# 5Vboostproto.net
KiCad netlist of a schematic drawn in EAGLE
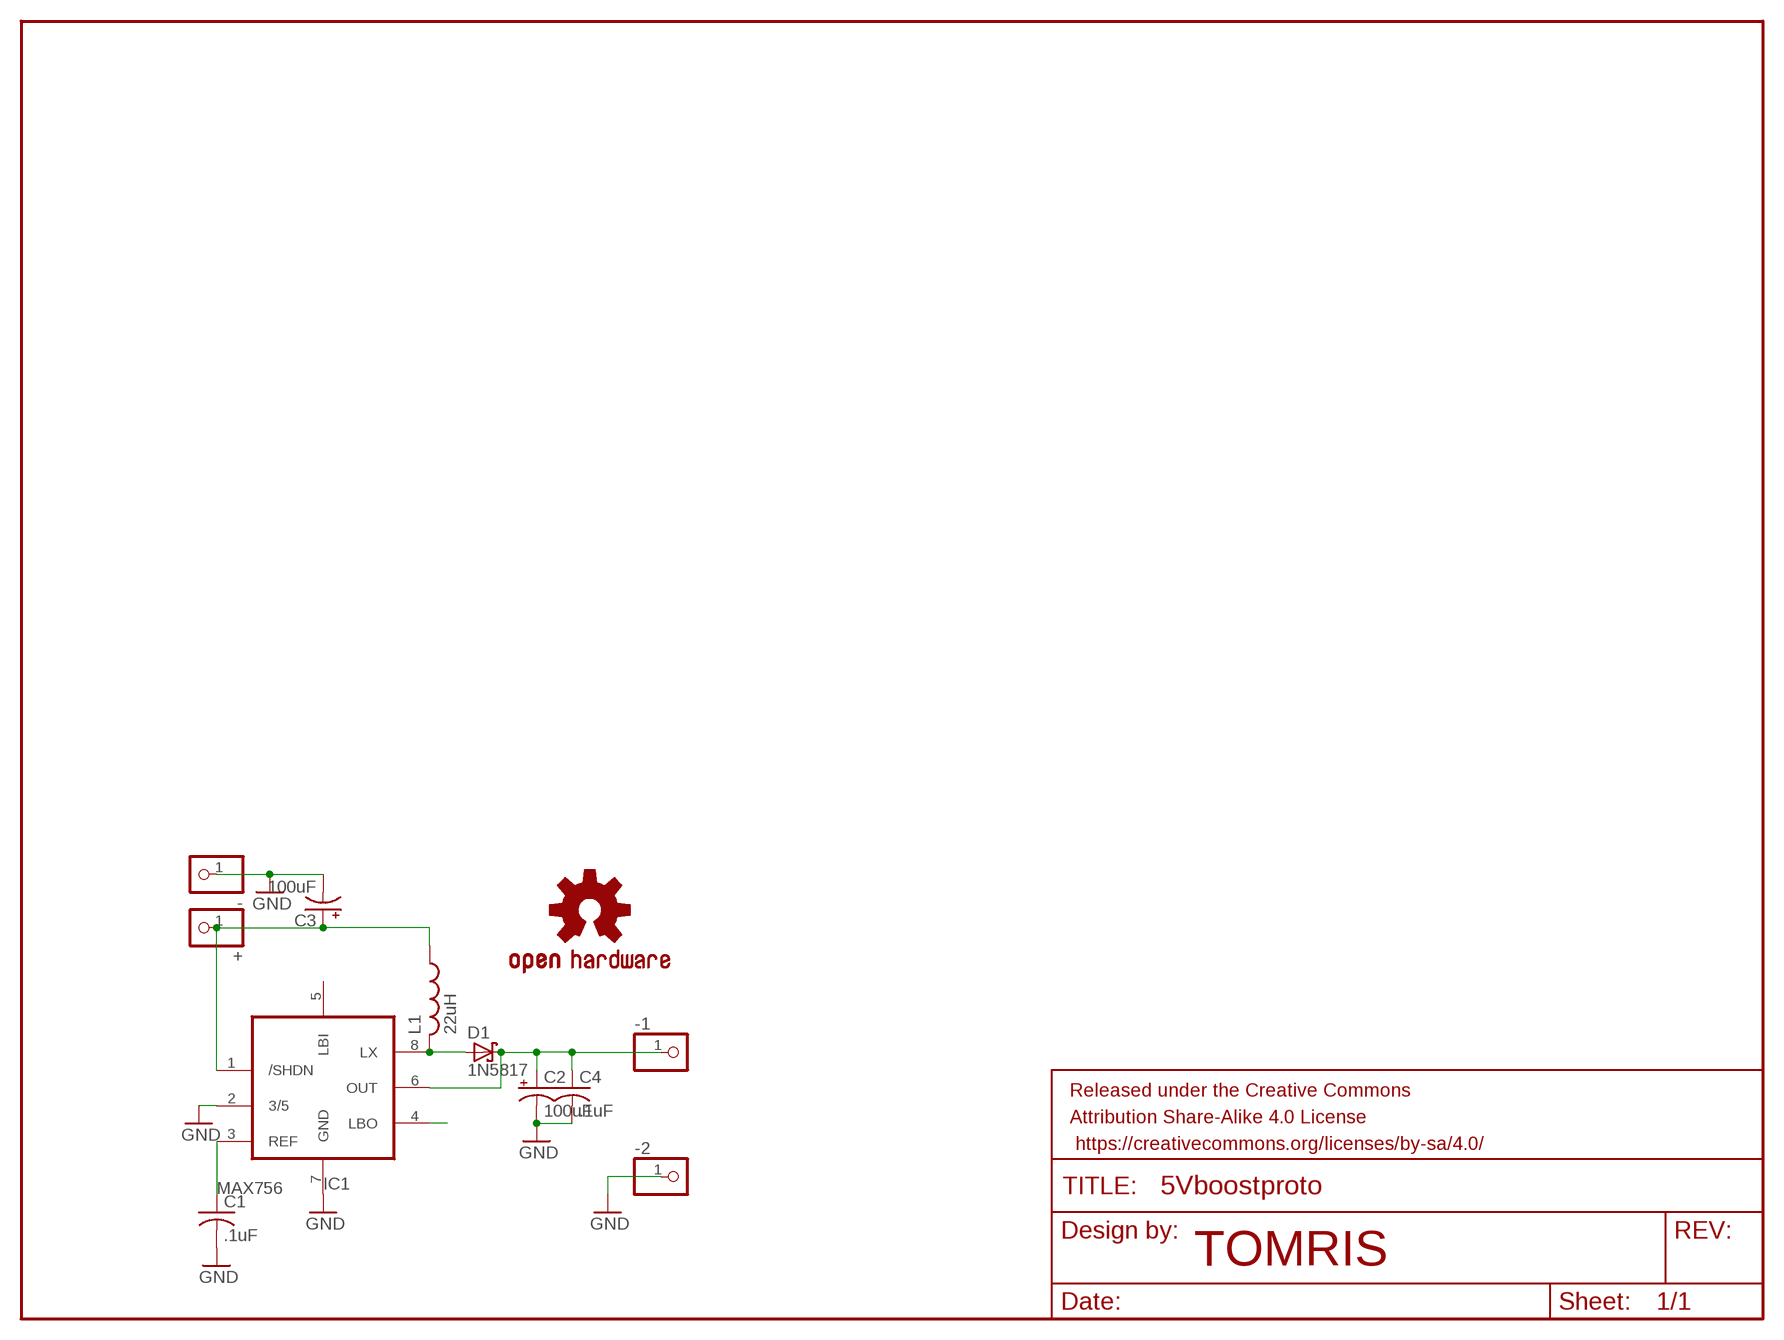
[diagram p0: schematic, sheet 1]

(export (version "E")
  (design (tool "Eeschema 10.0.6"))
  (components
    (comp (ref "+")
      (value "PINHD-1X1")
      (footprint "eagle-import:1X01")
      (libsource (lib "eagle-import") (part "PINHD-1X1"))
    )
    (comp (ref "-")
      (value "PINHD-1X1")
      (footprint "eagle-import:1X01")
      (libsource (lib "eagle-import") (part "PINHD-1X1"))
    )
    (comp (ref "-1")
      (value "PINHD-1X1")
      (footprint "eagle-import:1X01")
      (libsource (lib "eagle-import") (part "PINHD-1X1"))
    )
    (comp (ref "-2")
      (value "PINHD-1X1")
      (footprint "eagle-import:1X01")
      (libsource (lib "eagle-import") (part "PINHD-1X1"))
    )
    (comp (ref "C1")
      (value ".1uF")
      (footprint "eagle-import:C025-024X044")
      (libsource (lib "eagle-import") (part "C-US025-024X044"))
    )
    (comp (ref "C2")
      (value "100uF")
      (footprint "eagle-import:E2,5-5")
      (libsource (lib "eagle-import") (part "CPOL-USE2.5-5"))
    )
    (comp (ref "C3")
      (value "100uF")
      (footprint "eagle-import:E2,5-5")
      (libsource (lib "eagle-import") (part "CPOL-USE2.5-5"))
    )
    (comp (ref "C4")
      (value ".1uF")
      (footprint "eagle-import:C025-024X044")
      (libsource (lib "eagle-import") (part "C-US025-024X044"))
    )
    (comp (ref "D1")
      (value "1N5817")
      (footprint "eagle-import:DO41-10")
      (libsource (lib "eagle-import") (part "SCHOTTKY-DIODEDO41"))
    )
    (comp (ref "FRAME1")
      (value "FRAME-LETTER")
      (footprint "eagle-import:CREATIVE_COMMONS")
      (libsource (lib "eagle-import") (part "FRAME-LETTER"))
    )
    (comp (ref "IC1")
      (value "MAX756")
      (footprint "eagle-import:DIL08")
      (libsource (lib "eagle-import") (part "MAX756CPA"))
    )
    (comp (ref "L1")
      (value "22uH")
      (footprint "eagle-import:2747")
      (libsource (lib "eagle-import") (part "L2474/10"))
    )
    (comp (ref "LOGO1")
      (value "OSHW-LOGOM")
      (footprint "eagle-import:OSHW-LOGO-M")
      (libsource (lib "eagle-import") (part "OSHW-LOGOM"))
    )
  )
  (nets
    (net (code "1") (name "GND") (class "Default")
      (node (ref "-") (pin "1") (pinfunction "1_1") (pintype "passive"))
      (node (ref "-2") (pin "1") (pinfunction "1_1") (pintype "passive"))
      (node (ref "C1") (pin "2") (pinfunction "2_2") (pintype "passive"))
      (node (ref "C2") (pin "-") (pinfunction "-_-") (pintype "passive"))
      (node (ref "C3") (pin "-") (pinfunction "-_-") (pintype "passive"))
      (node (ref "C4") (pin "2") (pinfunction "2_2") (pintype "passive"))
      (node (ref "IC1") (pin "2") (pinfunction "3/5_2") (pintype "bidirectional"))
      (node (ref "IC1") (pin "7") (pinfunction "GND_7") (pintype "power_in"))
    )
    (net (code "2") (name "Net-(IC1-LX)") (class "Default")
      (node (ref "D1") (pin "A") (pinfunction "A_A") (pintype "passive"))
      (node (ref "IC1") (pin "8") (pinfunction "LX_8") (pintype "output"))
      (node (ref "L1") (pin "P$2") (pinfunction "2_P$2") (pintype "passive"))
    )
    (net (code "3") (name "Net-(IC1-OUT)") (class "Default")
      (node (ref "-1") (pin "1") (pinfunction "1_1") (pintype "passive"))
      (node (ref "C2") (pin "+") (pinfunction "+_+") (pintype "passive"))
      (node (ref "C4") (pin "1") (pinfunction "1_1") (pintype "passive"))
      (node (ref "D1") (pin "C") (pinfunction "C_C") (pintype "passive"))
      (node (ref "IC1") (pin "6") (pinfunction "OUT_6") (pintype "output"))
    )
    (net (code "4") (name "Net-(IC1-REF)") (class "Default")
      (node (ref "C1") (pin "1") (pinfunction "1_1") (pintype "passive"))
      (node (ref "IC1") (pin "3") (pinfunction "REF_3") (pintype "passive"))
    )
    (net (code "5") (name "Net-(IC1-{slash}SHDN)") (class "Default")
      (node (ref "+") (pin "1") (pinfunction "1_1") (pintype "passive"))
      (node (ref "C3") (pin "+") (pinfunction "+_+") (pintype "passive"))
      (node (ref "IC1") (pin "1") (pinfunction "/SHDN_1") (pintype "input"))
      (node (ref "L1") (pin "P$1") (pinfunction "1_P$1") (pintype "passive"))
    )
    (net (code "6") (name "unconnected-(IC1-LBI-Pad5)") (class "Default")
      (node (ref "IC1") (pin "5") (pinfunction "LBI_5") (pintype "input"))
    )
    (net (code "7") (name "unconnected-(IC1-LBO-Pad4)") (class "Default")
      (node (ref "IC1") (pin "4") (pinfunction "LBO_4") (pintype "input"))
    )
  )
)
